# AP64502Q_PINOUT.net
KiCad netlist of a schematic drawn in Altium Designer
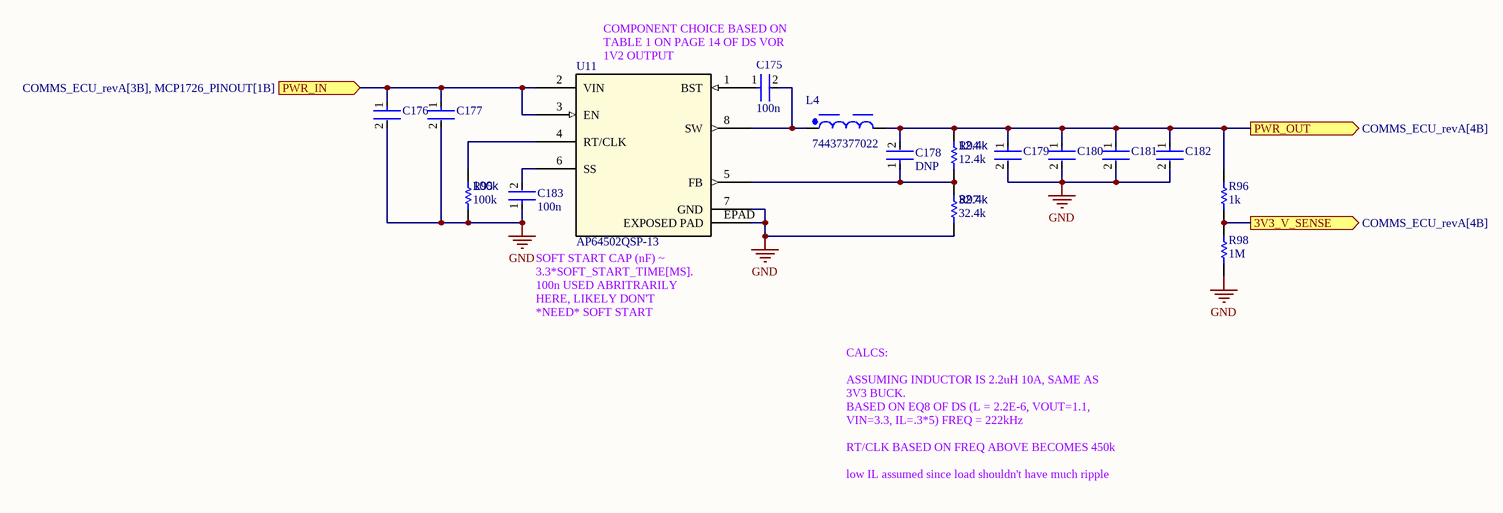
[diagram p0: AP64502Q_PINOUT.SchDoc]

(export (version "E")
  (design (tool "Eeschema 10.0.6"))
  (components
    (comp (ref "C175")
      (value "100n")
      (footprint "FP-0402-L_1_0_0_05-W_0_5-IPC_A")
      (description "LARGE PADS, 0402 CAP, CHANGE COMMENT TO MATCH REAL P/N")
      (libsource (lib "Space Concordia") (part "b4654b650e69147ec39a6b967a45e02"))
    )
    (comp (ref "C176")
      (value "12103D106KAT2A")
      (footprint "FP-1210-L_3_3_0_4-W_2_5_0-MFG")
      (description "General Purpose Ceramic Capacitor, 1210, 10uF, 10%, X5R, 15%, 25V")
      (fields (field (name "VOLTAGE") "25V") (field (name "TOLERANCE") "10%"))
      (libsource (lib "Altium Content Vault") (part "b4654b650e69147ec39a6b967a45e02"))
    )
    (comp (ref "C177")
      (value "12103D106KAT2A")
      (footprint "FP-1210-L_3_3_0_4-W_2_5_0-MFG")
      (description "General Purpose Ceramic Capacitor, 1210, 10uF, 10%, X5R, 15%, 25V")
      (fields (field (name "VOLTAGE") "25V") (field (name "TOLERANCE") "10%"))
      (libsource (lib "Altium Content Vault") (part "b4654b650e69147ec39a6b967a45e02"))
    )
    (comp (ref "C178")
      (value "DNP")
      (footprint "FP-0402-L_1_0_0_05-W_0_5-IPC_A")
      (description "LARGE PADS, 0402 CAP, CHANGE COMMENT TO MATCH REAL P/N")
      (libsource (lib "Space Concordia") (part "b4654b650e69147ec39a6b967a45e02"))
    )
    (comp (ref "C179")
      (value "CGA9N3X7R1C476M230KB")
      (footprint "FP-CGA9P-IPC_A")
      (description "Cap Ceramic 47uF 16V X7R 20% Pad SMD 2220 +125°C Automotive T/R")
      (fields (field (name "TOLERANCE") "20%"))
      (libsource (lib "Altium Content Vault") (part "b4654b650e69147ec39a6b967a45e02"))
    )
    (comp (ref "C180")
      (value "CGA9N3X7R1C476M230KB")
      (footprint "FP-CGA9P-IPC_A")
      (description "Cap Ceramic 47uF 16V X7R 20% Pad SMD 2220 +125°C Automotive T/R")
      (fields (field (name "TOLERANCE") "20%"))
      (libsource (lib "Altium Content Vault") (part "b4654b650e69147ec39a6b967a45e02"))
    )
    (comp (ref "C181")
      (value "CGA9N3X7R1C476M230KB")
      (footprint "FP-CGA9P-IPC_A")
      (description "Cap Ceramic 47uF 16V X7R 20% Pad SMD 2220 +125°C Automotive T/R")
      (fields (field (name "TOLERANCE") "20%"))
      (libsource (lib "Altium Content Vault") (part "b4654b650e69147ec39a6b967a45e02"))
    )
    (comp (ref "C182")
      (value "DNP")
      (footprint "FP-CGA9P-IPC_A")
      (description "Cap Ceramic 47uF 16V X7R 20% Pad SMD 2220 +125°C Automotive T/R")
      (fields (field (name "TOLERANCE") "20%"))
      (libsource (lib "Altium Content Vault") (part "b4654b650e69147ec39a6b967a45e02"))
    )
    (comp (ref "C183")
      (value "100n")
      (footprint "FP-0402-L_1_0_0_05-W_0_5-IPC_A")
      (description "LARGE PADS, 0402 CAP, CHANGE COMMENT TO MATCH REAL P/N")
      (libsource (lib "Space Concordia") (part "b4654b650e69147ec39a6b967a45e02"))
    )
    (comp (ref "L4")
      (value "74437377022")
      (footprint "WE-LHMI_1335")
      (fields (field (name "TOLERANCE") "20%"))
      (libsource (lib "Altium Content Vault") (part "Inductor - 2"))
    )
    (comp (ref "R94")
      (value "12.4k")
      (footprint "R0603B")
      (description "Resistor")
      (fields (field (name "ALTIUM_VALUE") "12.4k"))
      (libsource (lib "Space Concordia") (part "Resistor"))
    )
    (comp (ref "R95")
      (value "100k")
      (footprint "R0603B")
      (description "Resistor")
      (fields (field (name "ALTIUM_VALUE") "100k"))
      (libsource (lib "Space Concordia") (part "Resistor"))
    )
    (comp (ref "R96")
      (value "1k")
      (footprint "R0603B")
      (description "Resistor")
      (libsource (lib "Space Concordia") (part "Resistor"))
    )
    (comp (ref "R97")
      (value "32.4k")
      (footprint "R0603B")
      (description "Resistor")
      (fields (field (name "ALTIUM_VALUE") "32.4k"))
      (libsource (lib "Space Concordia") (part "Resistor"))
    )
    (comp (ref "R98")
      (value "1M")
      (footprint "R0603B")
      (description "Resistor")
      (libsource (lib "Space Concordia") (part "Resistor"))
    )
    (comp (ref "U11")
      (value "AP64502QSP-13")
      (footprint "SOIC127P600X163_HS-9N")
      (libsource (lib "Space Concordia") (part "AP64502QSP-13"))
    )
  )
  (nets
    (net (code "1") (name "/3V3_V_SENSE") (class "Default")
      (node (ref "R96") (pin "1") (pinfunction "1_1") (pintype "passive"))
      (node (ref "R98") (pin "2") (pinfunction "2_2") (pintype "passive"))
    )
    (net (code "2") (name "/PWR_IN") (class "Default")
      (node (ref "C176") (pin "1") (pinfunction "1_1") (pintype "passive"))
      (node (ref "C177") (pin "1") (pinfunction "1_1") (pintype "passive"))
      (node (ref "U11") (pin "2") (pinfunction "VIN_2") (pintype "power_in"))
      (node (ref "U11") (pin "3") (pinfunction "EN_3") (pintype "input"))
    )
    (net (code "3") (name "/PWR_OUT") (class "Default")
      (node (ref "C178") (pin "2") (pinfunction "2_2") (pintype "passive"))
      (node (ref "C179") (pin "1") (pinfunction "1_1") (pintype "passive"))
      (node (ref "C180") (pin "1") (pinfunction "1_1") (pintype "passive"))
      (node (ref "C181") (pin "1") (pinfunction "1_1") (pintype "passive"))
      (node (ref "C182") (pin "1") (pinfunction "1_1") (pintype "passive"))
      (node (ref "L4") (pin "2") (pinfunction "2_2") (pintype "passive"))
      (node (ref "R94") (pin "2") (pinfunction "2_2") (pintype "passive"))
      (node (ref "R96") (pin "2") (pinfunction "2_2") (pintype "passive"))
    )
    (net (code "4") (name "GND") (class "Default")
      (node (ref "C176") (pin "2") (pinfunction "2_2") (pintype "passive"))
      (node (ref "C177") (pin "2") (pinfunction "2_2") (pintype "passive"))
      (node (ref "C179") (pin "2") (pinfunction "2_2") (pintype "passive"))
      (node (ref "C180") (pin "2") (pinfunction "2_2") (pintype "passive"))
      (node (ref "C181") (pin "2") (pinfunction "2_2") (pintype "passive"))
      (node (ref "C182") (pin "2") (pinfunction "2_2") (pintype "passive"))
      (node (ref "C183") (pin "1") (pinfunction "1_1") (pintype "passive"))
      (node (ref "R95") (pin "1") (pinfunction "1_1") (pintype "passive"))
      (node (ref "R97") (pin "1") (pinfunction "1_1") (pintype "passive"))
      (node (ref "R98") (pin "1") (pinfunction "1_1") (pintype "passive"))
      (node (ref "U11") (pin "7") (pinfunction "GND_7") (pintype "power_in"))
      (node (ref "U11") (pin "EPAD") (pinfunction "EXPOSED_PAD_EPAD") (pintype "power_in"))
    )
    (net (code "5") (name "Net-(U11-BST)") (class "Default")
      (node (ref "C175") (pin "1") (pinfunction "1_1") (pintype "passive"))
      (node (ref "U11") (pin "1") (pinfunction "BST_1") (pintype "input"))
    )
    (net (code "6") (name "Net-(U11-FB)") (class "Default")
      (node (ref "C178") (pin "1") (pinfunction "1_1") (pintype "passive"))
      (node (ref "R94") (pin "1") (pinfunction "1_1") (pintype "passive"))
      (node (ref "R97") (pin "2") (pinfunction "2_2") (pintype "passive"))
      (node (ref "U11") (pin "5") (pinfunction "FB_5") (pintype "output"))
    )
    (net (code "7") (name "Net-(U11-RT{slash}CLK)") (class "Default")
      (node (ref "R95") (pin "2") (pinfunction "2_2") (pintype "passive"))
      (node (ref "U11") (pin "4") (pinfunction "RT/CLK_4") (pintype "passive"))
    )
    (net (code "8") (name "Net-(U11-SS)") (class "Default")
      (node (ref "C183") (pin "2") (pinfunction "2_2") (pintype "passive"))
      (node (ref "U11") (pin "6") (pinfunction "SS_6") (pintype "passive"))
    )
    (net (code "9") (name "Net-(U11-SW)") (class "Default")
      (node (ref "C175") (pin "2") (pinfunction "2_2") (pintype "passive"))
      (node (ref "L4") (pin "1") (pinfunction "1_1") (pintype "passive"))
      (node (ref "U11") (pin "8") (pinfunction "SW_8") (pintype "output"))
    )
  )
)
